# PumpSolBoardV2.net
KiCad netlist of a schematic drawn in EAGLE
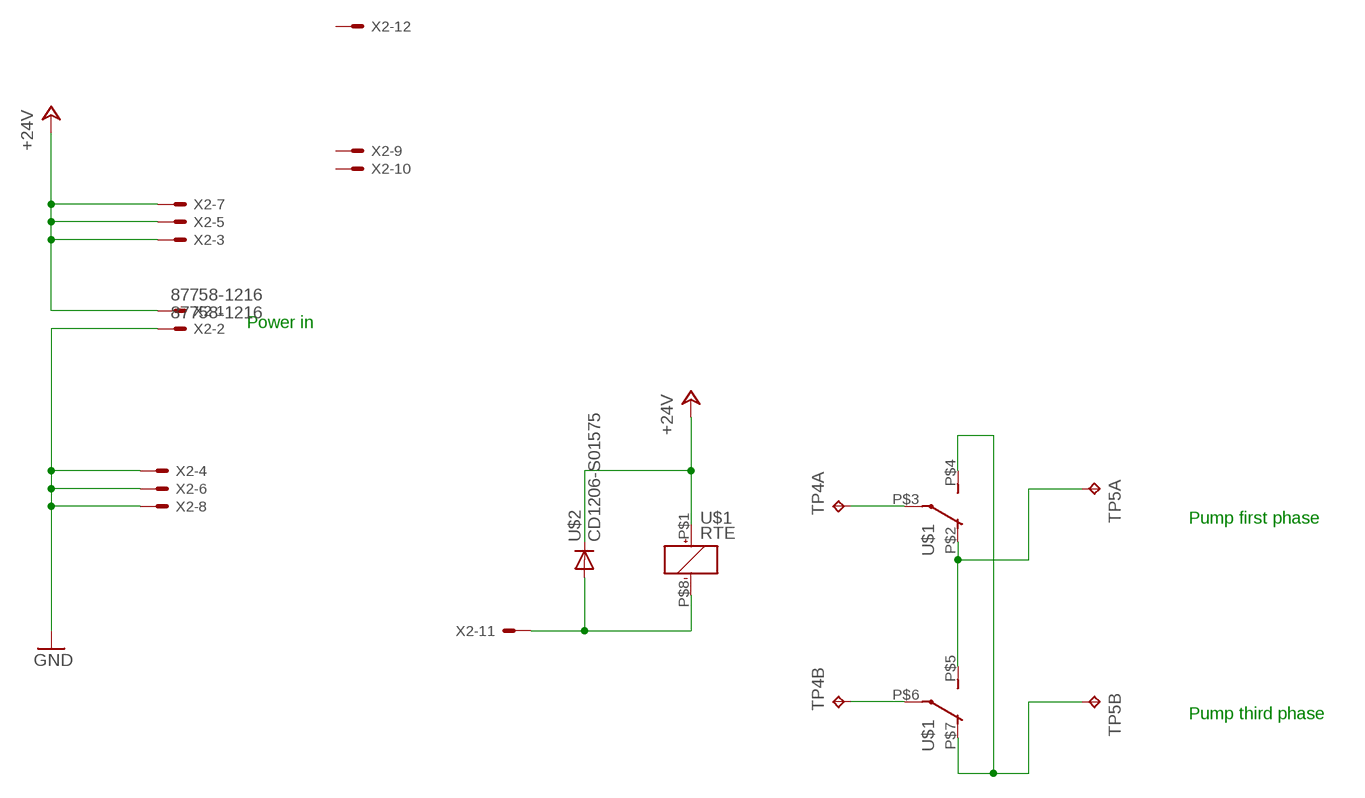
[diagram p0: schematic, sheet 1]

(export (version "E")
  (design (tool "Eeschema 10.0.6"))
  (components
    (comp (ref "TP4")
      (value "TP2P2-38-20")
      (footprint "eagle-import:P2-38-20")
      (libsource (lib "eagle-import") (part "TP2P2-38-20"))
    )
    (comp (ref "TP5")
      (value "TP2P2-38-20")
      (footprint "eagle-import:P2-38-20")
      (libsource (lib "eagle-import") (part "TP2P2-38-20"))
    )
    (comp (ref "U$1")
      (value "RTE")
      (footprint "eagle-import:RTE")
      (libsource (lib "eagle-import") (part "RTE"))
    )
    (comp (ref "U$2")
      (value "CD1206-S01575")
      (footprint "eagle-import:CD1206")
      (libsource (lib "eagle-import") (part "CD1206-S01575"))
    )
    (comp (ref "X2")
      (value "87758-1216")
      (footprint "eagle-import:87758-1216")
      (libsource (lib "eagle-import") (part "87758-1216"))
    )
  )
  (nets
    (net (code "1") (name "+24V") (class "Default")
      (node (ref "U$1") (pin "P$1") (pinfunction "+_P$1") (pintype "passive"))
      (node (ref "U$2") (pin "K") (pinfunction "C_K") (pintype "passive"))
      (node (ref "X2") (pin "1") (pinfunction "S_1") (pintype "passive"))
      (node (ref "X2") (pin "3") (pinfunction "S_3") (pintype "passive"))
      (node (ref "X2") (pin "5") (pinfunction "S_5") (pintype "passive"))
      (node (ref "X2") (pin "7") (pinfunction "S_7") (pintype "passive"))
    )
    (net (code "2") (name "GND") (class "Default")
      (node (ref "X2") (pin "2") (pinfunction "S_2") (pintype "passive"))
      (node (ref "X2") (pin "4") (pinfunction "S_4") (pintype "passive"))
      (node (ref "X2") (pin "6") (pinfunction "S_6") (pintype "passive"))
      (node (ref "X2") (pin "8") (pinfunction "S_8") (pintype "passive"))
    )
    (net (code "3") (name "Net-(TP4A-TP)") (class "Default")
      (node (ref "TP4") (pin "TP-1") (pinfunction "TP_TP-1") (pintype "input"))
      (node (ref "U$1") (pin "P$3") (pinfunction "P_P$3") (pintype "passive"))
    )
    (net (code "4") (name "Net-(TP4B-TP)") (class "Default")
      (node (ref "TP4") (pin "TP-2") (pinfunction "TP_TP-2") (pintype "input"))
      (node (ref "U$1") (pin "P$6") (pinfunction "P_P$6") (pintype "passive"))
    )
    (net (code "5") (name "Net-(TP5A-TP)") (class "Default")
      (node (ref "TP5") (pin "TP-1") (pinfunction "TP_TP-1") (pintype "input"))
      (node (ref "U$1") (pin "P$2") (pinfunction "O_P$2") (pintype "passive"))
      (node (ref "U$1") (pin "P$5") (pinfunction "S_P$5") (pintype "passive"))
    )
    (net (code "6") (name "Net-(TP5B-TP)") (class "Default")
      (node (ref "TP5") (pin "TP-2") (pinfunction "TP_TP-2") (pintype "input"))
      (node (ref "U$1") (pin "P$4") (pinfunction "S_P$4") (pintype "passive"))
      (node (ref "U$1") (pin "P$7") (pinfunction "O_P$7") (pintype "passive"))
    )
    (net (code "7") (name "Net-(U$1A--)") (class "Default")
      (node (ref "U$1") (pin "P$8") (pinfunction "-_P$8") (pintype "passive"))
      (node (ref "U$2") (pin "A") (pinfunction "A_A") (pintype "passive"))
      (node (ref "X2") (pin "11") (pinfunction "S_11") (pintype "passive"))
    )
    (net (code "8") (name "unconnected-(X2B-S-Pad10)") (class "Default")
      (node (ref "X2") (pin "10") (pinfunction "S_10") (pintype "passive"))
    )
    (net (code "9") (name "unconnected-(X2D-S-Pad12)") (class "Default")
      (node (ref "X2") (pin "12") (pinfunction "S_12") (pintype "passive"))
    )
    (net (code "10") (name "unconnected-(X2L-S-Pad9)") (class "Default")
      (node (ref "X2") (pin "9") (pinfunction "S_9") (pintype "passive"))
    )
  )
)
